# M161.net
KiCad netlist of a schematic drawn in EAGLE
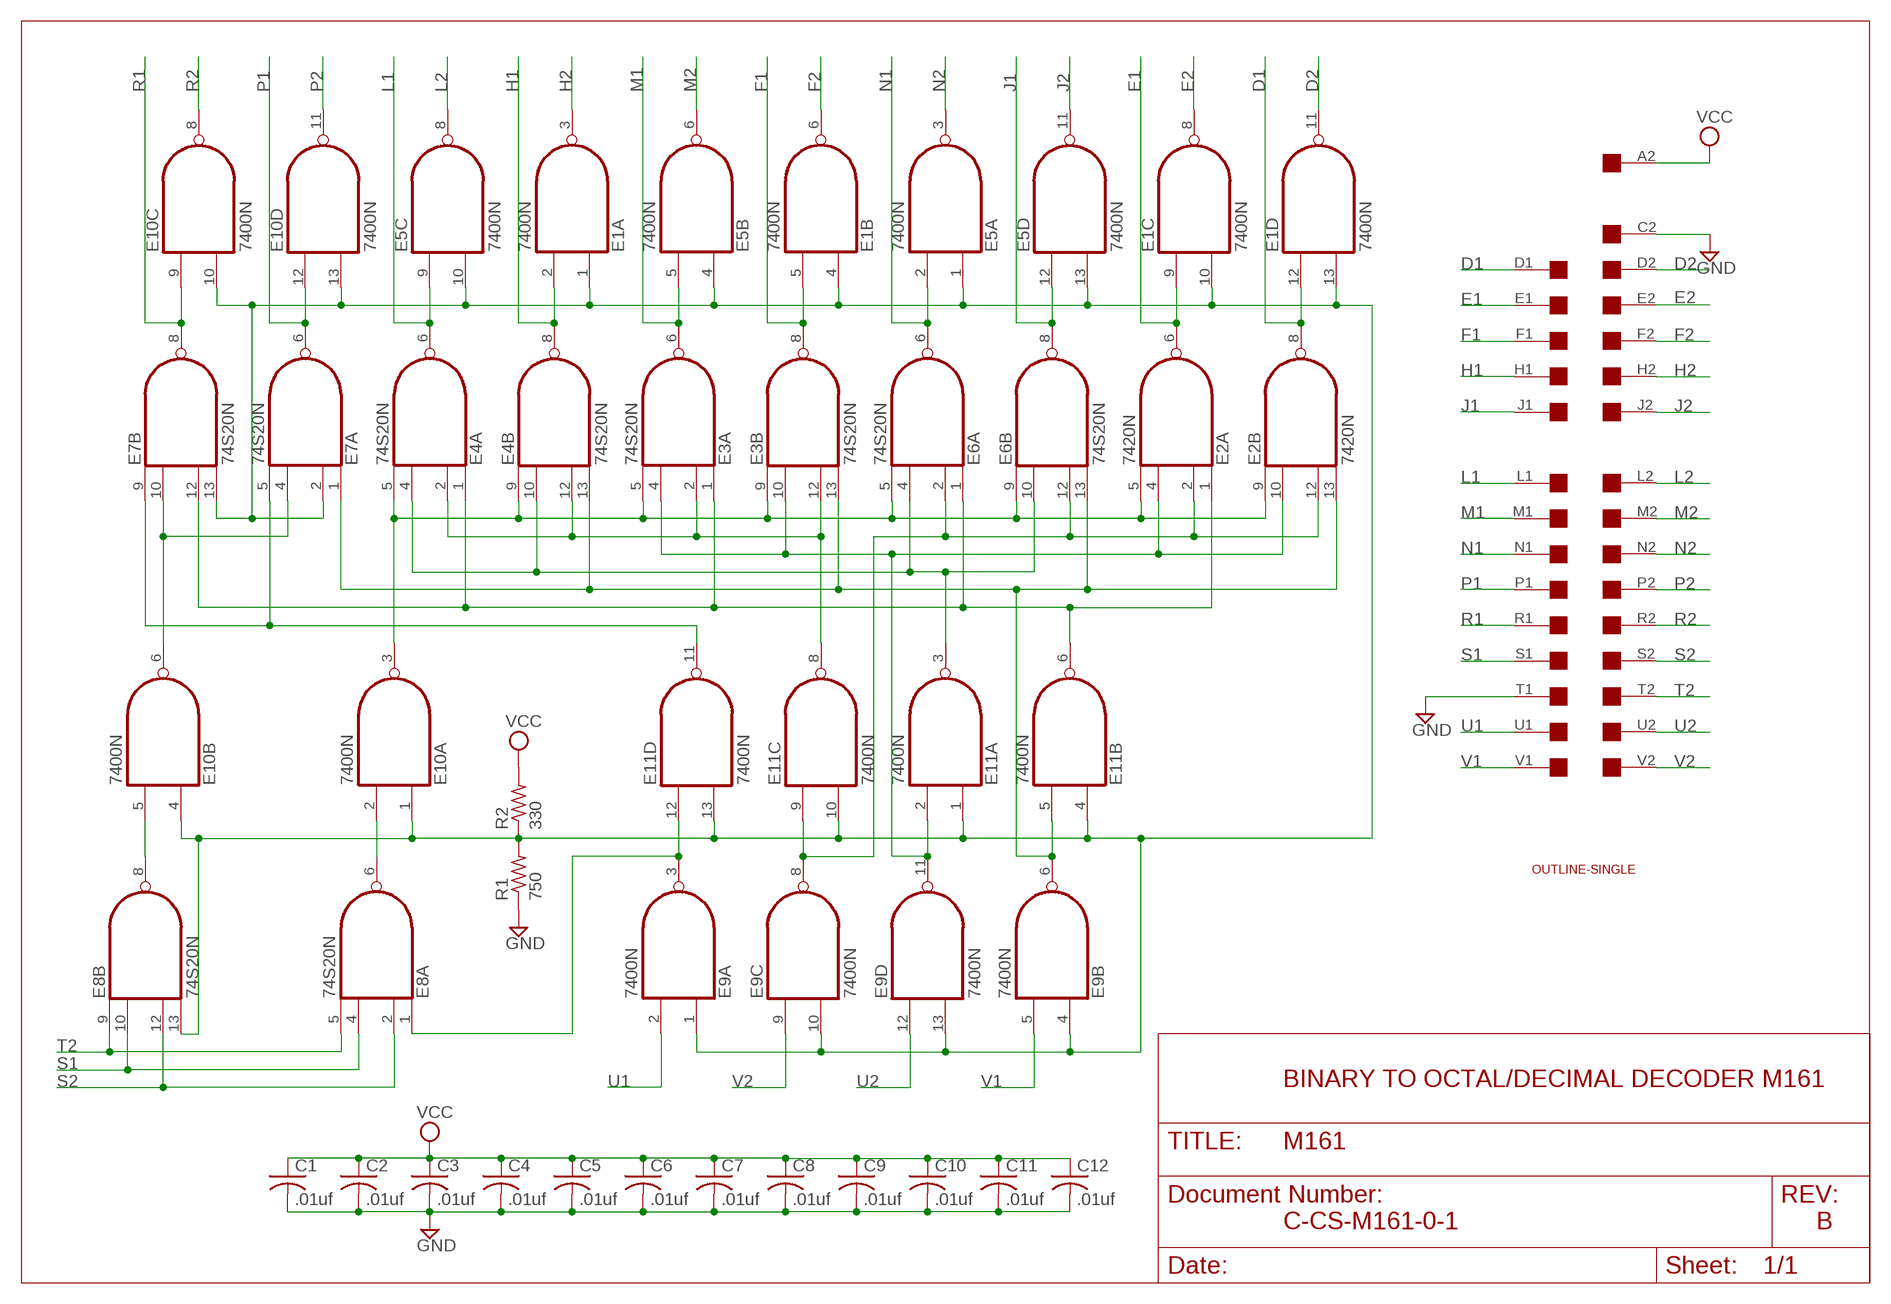
[diagram p0: schematic, sheet 1]

(export (version "E")
  (design (tool "Eeschema 10.0.6"))
  (components
    (comp (ref "C1")
      (value ".01uf")
      (footprint "eagle-import:C050-025X075")
      (libsource (lib "eagle-import") (part "C-US050-025X075"))
    )
    (comp (ref "C2")
      (value ".01uf")
      (footprint "eagle-import:C050-025X075")
      (libsource (lib "eagle-import") (part "C-US050-025X075"))
    )
    (comp (ref "C3")
      (value ".01uf")
      (footprint "eagle-import:C050-025X075")
      (libsource (lib "eagle-import") (part "C-US050-025X075"))
    )
    (comp (ref "C4")
      (value ".01uf")
      (footprint "eagle-import:C050-025X075")
      (libsource (lib "eagle-import") (part "C-US050-025X075"))
    )
    (comp (ref "C5")
      (value ".01uf")
      (footprint "eagle-import:C050-025X075")
      (libsource (lib "eagle-import") (part "C-US050-025X075"))
    )
    (comp (ref "C6")
      (value ".01uf")
      (footprint "eagle-import:C050-025X075")
      (libsource (lib "eagle-import") (part "C-US050-025X075"))
    )
    (comp (ref "C7")
      (value ".01uf")
      (footprint "eagle-import:C050-025X075")
      (libsource (lib "eagle-import") (part "C-US050-025X075"))
    )
    (comp (ref "C8")
      (value ".01uf")
      (footprint "eagle-import:C050-025X075")
      (libsource (lib "eagle-import") (part "C-US050-025X075"))
    )
    (comp (ref "C9")
      (value ".01uf")
      (footprint "eagle-import:C050-025X075")
      (libsource (lib "eagle-import") (part "C-US050-025X075"))
    )
    (comp (ref "C10")
      (value ".01uf")
      (footprint "eagle-import:C050-025X075")
      (libsource (lib "eagle-import") (part "C-US050-025X075"))
    )
    (comp (ref "C11")
      (value ".01uf")
      (footprint "eagle-import:C050-025X075")
      (libsource (lib "eagle-import") (part "C-US050-025X075"))
    )
    (comp (ref "C12")
      (value ".01uf")
      (footprint "eagle-import:C050-025X075")
      (libsource (lib "eagle-import") (part "C-US050-025X075"))
    )
    (comp (ref "E1")
      (value "7400N")
      (footprint "eagle-import:DIL14")
      (libsource (lib "eagle-import") (part "7400N"))
    )
    (comp (ref "E2")
      (value "7420N")
      (footprint "eagle-import:DIL14")
      (libsource (lib "eagle-import") (part "7420NS"))
    )
    (comp (ref "E3")
      (value "74S20N")
      (footprint "eagle-import:DIL14")
      (libsource (lib "eagle-import") (part "7420NS"))
    )
    (comp (ref "E4")
      (value "74S20N")
      (footprint "eagle-import:DIL14")
      (libsource (lib "eagle-import") (part "7420NS"))
    )
    (comp (ref "E5")
      (value "7400N")
      (footprint "eagle-import:DIL14")
      (libsource (lib "eagle-import") (part "7400N"))
    )
    (comp (ref "E6")
      (value "74S20N")
      (footprint "eagle-import:DIL14")
      (libsource (lib "eagle-import") (part "7420NS"))
    )
    (comp (ref "E7")
      (value "74S20N")
      (footprint "eagle-import:DIL14")
      (libsource (lib "eagle-import") (part "7420NS"))
    )
    (comp (ref "E8")
      (value "74S20N")
      (footprint "eagle-import:DIL14")
      (libsource (lib "eagle-import") (part "7420NS"))
    )
    (comp (ref "E9")
      (value "7400N")
      (footprint "eagle-import:DIL14")
      (libsource (lib "eagle-import") (part "7400N"))
    )
    (comp (ref "E10")
      (value "7400N")
      (footprint "eagle-import:DIL14")
      (libsource (lib "eagle-import") (part "7400N"))
    )
    (comp (ref "E11")
      (value "7400N")
      (footprint "eagle-import:DIL14")
      (libsource (lib "eagle-import") (part "7400N"))
    )
    (comp (ref "R1")
      (value "750")
      (footprint "eagle-import:0207_10")
      (libsource (lib "eagle-import") (part "R-US_0207/10"))
    )
    (comp (ref "R2")
      (value "330")
      (footprint "eagle-import:0207_10")
      (libsource (lib "eagle-import") (part "R-US_0207/10"))
    )
    (comp (ref "U$1")
      (value "OUTLINE-SINGLE")
      (footprint "eagle-import:SINGLE")
      (libsource (lib "eagle-import") (part "OUTLINE-SINGLE"))
    )
    (comp (ref "U$4")
      (value "SINGLE")
      (footprint "eagle-import:EDGE-CON2")
      (libsource (lib "eagle-import") (part "SINGLE"))
    )
  )
  (nets
    (net (code "1") (name "/D1") (class "Default")
      (node (ref "E1") (pin "12") (pinfunction "I0_12") (pintype "input"))
      (node (ref "E2") (pin "8") (pinfunction "O_8") (pintype "output"))
      (node (ref "U$4") (pin "D1") (pinfunction "1_D1") (pintype "bidirectional"))
    )
    (net (code "2") (name "/D2") (class "Default")
      (node (ref "E1") (pin "11") (pinfunction "O_11") (pintype "output"))
      (node (ref "U$4") (pin "D2") (pinfunction "1_D2") (pintype "bidirectional"))
    )
    (net (code "3") (name "/E1") (class "Default")
      (node (ref "E1") (pin "9") (pinfunction "I0_9") (pintype "input"))
      (node (ref "E2") (pin "6") (pinfunction "O_6") (pintype "output"))
      (node (ref "U$4") (pin "E1") (pinfunction "1_E1") (pintype "bidirectional"))
    )
    (net (code "4") (name "/E2") (class "Default")
      (node (ref "E1") (pin "8") (pinfunction "O_8") (pintype "output"))
      (node (ref "U$4") (pin "E2") (pinfunction "1_E2") (pintype "bidirectional"))
    )
    (net (code "5") (name "/F1") (class "Default")
      (node (ref "E1") (pin "5") (pinfunction "I1_5") (pintype "input"))
      (node (ref "E3") (pin "8") (pinfunction "O_8") (pintype "output"))
      (node (ref "U$4") (pin "F1") (pinfunction "1_F1") (pintype "bidirectional"))
    )
    (net (code "6") (name "/F2") (class "Default")
      (node (ref "E1") (pin "6") (pinfunction "O_6") (pintype "output"))
      (node (ref "U$4") (pin "F2") (pinfunction "1_F2") (pintype "bidirectional"))
    )
    (net (code "7") (name "/H1") (class "Default")
      (node (ref "E1") (pin "2") (pinfunction "I1_2") (pintype "input"))
      (node (ref "E4") (pin "8") (pinfunction "O_8") (pintype "output"))
      (node (ref "U$4") (pin "H1") (pinfunction "1_H1") (pintype "bidirectional"))
    )
    (net (code "8") (name "/H2") (class "Default")
      (node (ref "E1") (pin "3") (pinfunction "O_3") (pintype "output"))
      (node (ref "U$4") (pin "H2") (pinfunction "1_H2") (pintype "bidirectional"))
    )
    (net (code "9") (name "/J1") (class "Default")
      (node (ref "E5") (pin "12") (pinfunction "I0_12") (pintype "input"))
      (node (ref "E6") (pin "8") (pinfunction "O_8") (pintype "output"))
      (node (ref "U$4") (pin "J1") (pinfunction "1_J1") (pintype "bidirectional"))
    )
    (net (code "10") (name "/J2") (class "Default")
      (node (ref "E5") (pin "11") (pinfunction "O_11") (pintype "output"))
      (node (ref "U$4") (pin "J2") (pinfunction "1_J2") (pintype "bidirectional"))
    )
    (net (code "11") (name "/L1") (class "Default")
      (node (ref "E4") (pin "6") (pinfunction "O_6") (pintype "output"))
      (node (ref "E5") (pin "9") (pinfunction "I0_9") (pintype "input"))
      (node (ref "U$4") (pin "L1") (pinfunction "1_L1") (pintype "bidirectional"))
    )
    (net (code "12") (name "/L2") (class "Default")
      (node (ref "E5") (pin "8") (pinfunction "O_8") (pintype "output"))
      (node (ref "U$4") (pin "L2") (pinfunction "1_L2") (pintype "bidirectional"))
    )
    (net (code "13") (name "/M1") (class "Default")
      (node (ref "E3") (pin "6") (pinfunction "O_6") (pintype "output"))
      (node (ref "E5") (pin "5") (pinfunction "I1_5") (pintype "input"))
      (node (ref "U$4") (pin "M1") (pinfunction "1_M1") (pintype "bidirectional"))
    )
    (net (code "14") (name "/M2") (class "Default")
      (node (ref "E5") (pin "6") (pinfunction "O_6") (pintype "output"))
      (node (ref "U$4") (pin "M2") (pinfunction "1_M2") (pintype "bidirectional"))
    )
    (net (code "15") (name "/N1") (class "Default")
      (node (ref "E5") (pin "2") (pinfunction "I1_2") (pintype "input"))
      (node (ref "E6") (pin "6") (pinfunction "O_6") (pintype "output"))
      (node (ref "U$4") (pin "N1") (pinfunction "1_N1") (pintype "bidirectional"))
    )
    (net (code "16") (name "/N2") (class "Default")
      (node (ref "E5") (pin "3") (pinfunction "O_3") (pintype "output"))
      (node (ref "U$4") (pin "N2") (pinfunction "1_N2") (pintype "bidirectional"))
    )
    (net (code "17") (name "/P1") (class "Default")
      (node (ref "E10") (pin "12") (pinfunction "I0_12") (pintype "input"))
      (node (ref "E7") (pin "6") (pinfunction "O_6") (pintype "output"))
      (node (ref "U$4") (pin "P1") (pinfunction "1_P1") (pintype "bidirectional"))
    )
    (net (code "18") (name "/P2") (class "Default")
      (node (ref "E10") (pin "11") (pinfunction "O_11") (pintype "output"))
      (node (ref "U$4") (pin "P2") (pinfunction "1_P2") (pintype "bidirectional"))
    )
    (net (code "19") (name "/R1") (class "Default")
      (node (ref "E10") (pin "9") (pinfunction "I0_9") (pintype "input"))
      (node (ref "E7") (pin "8") (pinfunction "O_8") (pintype "output"))
      (node (ref "U$4") (pin "R1") (pinfunction "1_R1") (pintype "bidirectional"))
    )
    (net (code "20") (name "/R2") (class "Default")
      (node (ref "E10") (pin "8") (pinfunction "O_8") (pintype "output"))
      (node (ref "U$4") (pin "R2") (pinfunction "1_R2") (pintype "bidirectional"))
    )
    (net (code "21") (name "/S1") (class "Default")
      (node (ref "E8") (pin "10") (pinfunction "I1_10") (pintype "input"))
      (node (ref "E8") (pin "4") (pinfunction "I2_4") (pintype "input"))
      (node (ref "U$4") (pin "S1") (pinfunction "1_S1") (pintype "bidirectional"))
    )
    (net (code "22") (name "/S2") (class "Default")
      (node (ref "E8") (pin "12") (pinfunction "I2_12") (pintype "input"))
      (node (ref "E8") (pin "2") (pinfunction "I1_2") (pintype "input"))
      (node (ref "U$4") (pin "S2") (pinfunction "1_S2") (pintype "bidirectional"))
    )
    (net (code "23") (name "/T2") (class "Default")
      (node (ref "E8") (pin "5") (pinfunction "I3_5") (pintype "input"))
      (node (ref "E8") (pin "9") (pinfunction "I0_9") (pintype "input"))
      (node (ref "U$4") (pin "T2") (pinfunction "1_T2") (pintype "bidirectional"))
    )
    (net (code "24") (name "/U1") (class "Default")
      (node (ref "E9") (pin "2") (pinfunction "I1_2") (pintype "input"))
      (node (ref "U$4") (pin "U1") (pinfunction "1_U1") (pintype "bidirectional"))
    )
    (net (code "25") (name "/U2") (class "Default")
      (node (ref "E9") (pin "12") (pinfunction "I0_12") (pintype "input"))
      (node (ref "U$4") (pin "U2") (pinfunction "1_U2") (pintype "bidirectional"))
    )
    (net (code "26") (name "/V1") (class "Default")
      (node (ref "E9") (pin "5") (pinfunction "I1_5") (pintype "input"))
      (node (ref "U$4") (pin "V1") (pinfunction "1_V1") (pintype "bidirectional"))
    )
    (net (code "27") (name "/V2") (class "Default")
      (node (ref "E9") (pin "9") (pinfunction "I0_9") (pintype "input"))
      (node (ref "U$4") (pin "V2") (pinfunction "1_V2") (pintype "bidirectional"))
    )
    (net (code "28") (name "GND") (class "Default")
      (node (ref "C1") (pin "2") (pinfunction "2_2") (pintype "passive"))
      (node (ref "C10") (pin "2") (pinfunction "2_2") (pintype "passive"))
      (node (ref "C11") (pin "2") (pinfunction "2_2") (pintype "passive"))
      (node (ref "C12") (pin "2") (pinfunction "2_2") (pintype "passive"))
      (node (ref "C2") (pin "2") (pinfunction "2_2") (pintype "passive"))
      (node (ref "C3") (pin "2") (pinfunction "2_2") (pintype "passive"))
      (node (ref "C4") (pin "2") (pinfunction "2_2") (pintype "passive"))
      (node (ref "C5") (pin "2") (pinfunction "2_2") (pintype "passive"))
      (node (ref "C6") (pin "2") (pinfunction "2_2") (pintype "passive"))
      (node (ref "C7") (pin "2") (pinfunction "2_2") (pintype "passive"))
      (node (ref "C8") (pin "2") (pinfunction "2_2") (pintype "passive"))
      (node (ref "C9") (pin "2") (pinfunction "2_2") (pintype "passive"))
      (node (ref "R1") (pin "1") (pinfunction "1_1") (pintype "passive"))
      (node (ref "U$4") (pin "C2") (pinfunction "1_C2") (pintype "bidirectional"))
      (node (ref "U$4") (pin "T1") (pinfunction "1_T1") (pintype "bidirectional"))
    )
    (net (code "29") (name "Net-(E10A-I0)") (class "Default")
      (node (ref "E1") (pin "1") (pinfunction "I0_1") (pintype "input"))
      (node (ref "E1") (pin "10") (pinfunction "I1_10") (pintype "input"))
      (node (ref "E1") (pin "13") (pinfunction "I1_13") (pintype "input"))
      (node (ref "E1") (pin "4") (pinfunction "I0_4") (pintype "input"))
      (node (ref "E10") (pin "1") (pinfunction "I0_1") (pintype "input"))
      (node (ref "E10") (pin "10") (pinfunction "I1_10") (pintype "input"))
      (node (ref "E10") (pin "13") (pinfunction "I1_13") (pintype "input"))
      (node (ref "E10") (pin "4") (pinfunction "I0_4") (pintype "input"))
      (node (ref "E11") (pin "1") (pinfunction "I0_1") (pintype "input"))
      (node (ref "E11") (pin "10") (pinfunction "I1_10") (pintype "input"))
      (node (ref "E11") (pin "13") (pinfunction "I1_13") (pintype "input"))
      (node (ref "E11") (pin "4") (pinfunction "I0_4") (pintype "input"))
      (node (ref "E5") (pin "1") (pinfunction "I0_1") (pintype "input"))
      (node (ref "E5") (pin "10") (pinfunction "I1_10") (pintype "input"))
      (node (ref "E5") (pin "13") (pinfunction "I1_13") (pintype "input"))
      (node (ref "E5") (pin "4") (pinfunction "I0_4") (pintype "input"))
      (node (ref "E7") (pin "13") (pinfunction "I3_13") (pintype "input"))
      (node (ref "E7") (pin "2") (pinfunction "I1_2") (pintype "input"))
      (node (ref "E8") (pin "13") (pinfunction "I3_13") (pintype "input"))
      (node (ref "E9") (pin "1") (pinfunction "I0_1") (pintype "input"))
      (node (ref "E9") (pin "10") (pinfunction "I1_10") (pintype "input"))
      (node (ref "E9") (pin "13") (pinfunction "I1_13") (pintype "input"))
      (node (ref "E9") (pin "4") (pinfunction "I0_4") (pintype "input"))
      (node (ref "R1") (pin "2") (pinfunction "2_2") (pintype "passive"))
      (node (ref "R2") (pin "1") (pinfunction "1_1") (pintype "passive"))
    )
    (net (code "30") (name "Net-(E10A-I1)") (class "Default")
      (node (ref "E10") (pin "2") (pinfunction "I1_2") (pintype "input"))
      (node (ref "E8") (pin "6") (pinfunction "O_6") (pintype "output"))
    )
    (net (code "31") (name "Net-(E10A-O)") (class "Default")
      (node (ref "E10") (pin "3") (pinfunction "O_3") (pintype "output"))
      (node (ref "E2") (pin "5") (pinfunction "I3_5") (pintype "input"))
      (node (ref "E2") (pin "9") (pinfunction "I0_9") (pintype "input"))
      (node (ref "E3") (pin "5") (pinfunction "I3_5") (pintype "input"))
      (node (ref "E3") (pin "9") (pinfunction "I0_9") (pintype "input"))
      (node (ref "E4") (pin "5") (pinfunction "I3_5") (pintype "input"))
      (node (ref "E4") (pin "9") (pinfunction "I0_9") (pintype "input"))
      (node (ref "E6") (pin "5") (pinfunction "I3_5") (pintype "input"))
      (node (ref "E6") (pin "9") (pinfunction "I0_9") (pintype "input"))
    )
    (net (code "32") (name "Net-(E10B-I1)") (class "Default")
      (node (ref "E10") (pin "5") (pinfunction "I1_5") (pintype "input"))
      (node (ref "E8") (pin "8") (pinfunction "O_8") (pintype "output"))
    )
    (net (code "33") (name "Net-(E10B-O)") (class "Default")
      (node (ref "E10") (pin "6") (pinfunction "O_6") (pintype "output"))
      (node (ref "E7") (pin "10") (pinfunction "I1_10") (pintype "input"))
      (node (ref "E7") (pin "4") (pinfunction "I2_4") (pintype "input"))
    )
    (net (code "34") (name "Net-(E11A-I1)") (class "Default")
      (node (ref "E11") (pin "2") (pinfunction "I1_2") (pintype "input"))
      (node (ref "E2") (pin "10") (pinfunction "I1_10") (pintype "input"))
      (node (ref "E2") (pin "4") (pinfunction "I2_4") (pintype "input"))
      (node (ref "E3") (pin "10") (pinfunction "I1_10") (pintype "input"))
      (node (ref "E3") (pin "4") (pinfunction "I2_4") (pintype "input"))
      (node (ref "E9") (pin "11") (pinfunction "O_11") (pintype "output"))
    )
    (net (code "35") (name "Net-(E11A-O)") (class "Default")
      (node (ref "E11") (pin "3") (pinfunction "O_3") (pintype "output"))
      (node (ref "E4") (pin "10") (pinfunction "I1_10") (pintype "input"))
      (node (ref "E4") (pin "4") (pinfunction "I2_4") (pintype "input"))
      (node (ref "E6") (pin "10") (pinfunction "I1_10") (pintype "input"))
      (node (ref "E6") (pin "4") (pinfunction "I2_4") (pintype "input"))
    )
    (net (code "36") (name "Net-(E11B-I1)") (class "Default")
      (node (ref "E11") (pin "5") (pinfunction "I1_5") (pintype "input"))
      (node (ref "E2") (pin "13") (pinfunction "I3_13") (pintype "input"))
      (node (ref "E3") (pin "13") (pinfunction "I3_13") (pintype "input"))
      (node (ref "E4") (pin "13") (pinfunction "I3_13") (pintype "input"))
      (node (ref "E6") (pin "13") (pinfunction "I3_13") (pintype "input"))
      (node (ref "E7") (pin "1") (pinfunction "I0_1") (pintype "input"))
      (node (ref "E9") (pin "6") (pinfunction "O_6") (pintype "output"))
    )
    (net (code "37") (name "Net-(E11B-O)") (class "Default")
      (node (ref "E11") (pin "6") (pinfunction "O_6") (pintype "output"))
      (node (ref "E2") (pin "1") (pinfunction "I0_1") (pintype "input"))
      (node (ref "E3") (pin "1") (pinfunction "I0_1") (pintype "input"))
      (node (ref "E4") (pin "1") (pinfunction "I0_1") (pintype "input"))
      (node (ref "E6") (pin "1") (pinfunction "I0_1") (pintype "input"))
      (node (ref "E7") (pin "12") (pinfunction "I2_12") (pintype "input"))
    )
    (net (code "38") (name "Net-(E11C-I0)") (class "Default")
      (node (ref "E11") (pin "9") (pinfunction "I0_9") (pintype "input"))
      (node (ref "E2") (pin "12") (pinfunction "I2_12") (pintype "input"))
      (node (ref "E2") (pin "2") (pinfunction "I1_2") (pintype "input"))
      (node (ref "E6") (pin "12") (pinfunction "I2_12") (pintype "input"))
      (node (ref "E6") (pin "2") (pinfunction "I1_2") (pintype "input"))
      (node (ref "E9") (pin "8") (pinfunction "O_8") (pintype "output"))
    )
    (net (code "39") (name "Net-(E11C-O)") (class "Default")
      (node (ref "E11") (pin "8") (pinfunction "O_8") (pintype "output"))
      (node (ref "E3") (pin "12") (pinfunction "I2_12") (pintype "input"))
      (node (ref "E3") (pin "2") (pinfunction "I1_2") (pintype "input"))
      (node (ref "E4") (pin "12") (pinfunction "I2_12") (pintype "input"))
      (node (ref "E4") (pin "2") (pinfunction "I1_2") (pintype "input"))
    )
    (net (code "40") (name "Net-(E11D-I0)") (class "Default")
      (node (ref "E11") (pin "12") (pinfunction "I0_12") (pintype "input"))
      (node (ref "E8") (pin "1") (pinfunction "I0_1") (pintype "input"))
      (node (ref "E9") (pin "3") (pinfunction "O_3") (pintype "output"))
    )
    (net (code "41") (name "Net-(E11D-O)") (class "Default")
      (node (ref "E11") (pin "11") (pinfunction "O_11") (pintype "output"))
      (node (ref "E7") (pin "5") (pinfunction "I3_5") (pintype "input"))
      (node (ref "E7") (pin "9") (pinfunction "I0_9") (pintype "input"))
    )
    (net (code "42") (name "VCC") (class "Default")
      (node (ref "C1") (pin "1") (pinfunction "1_1") (pintype "passive"))
      (node (ref "C10") (pin "1") (pinfunction "1_1") (pintype "passive"))
      (node (ref "C11") (pin "1") (pinfunction "1_1") (pintype "passive"))
      (node (ref "C12") (pin "1") (pinfunction "1_1") (pintype "passive"))
      (node (ref "C2") (pin "1") (pinfunction "1_1") (pintype "passive"))
      (node (ref "C3") (pin "1") (pinfunction "1_1") (pintype "passive"))
      (node (ref "C4") (pin "1") (pinfunction "1_1") (pintype "passive"))
      (node (ref "C5") (pin "1") (pinfunction "1_1") (pintype "passive"))
      (node (ref "C6") (pin "1") (pinfunction "1_1") (pintype "passive"))
      (node (ref "C7") (pin "1") (pinfunction "1_1") (pintype "passive"))
      (node (ref "C8") (pin "1") (pinfunction "1_1") (pintype "passive"))
      (node (ref "C9") (pin "1") (pinfunction "1_1") (pintype "passive"))
      (node (ref "R2") (pin "2") (pinfunction "2_2") (pintype "passive"))
      (node (ref "U$4") (pin "A2") (pinfunction "1_A2") (pintype "bidirectional"))
    )
  )
)
